# Youtube_Top.net
KiCad netlist of a schematic drawn in Altium Designer
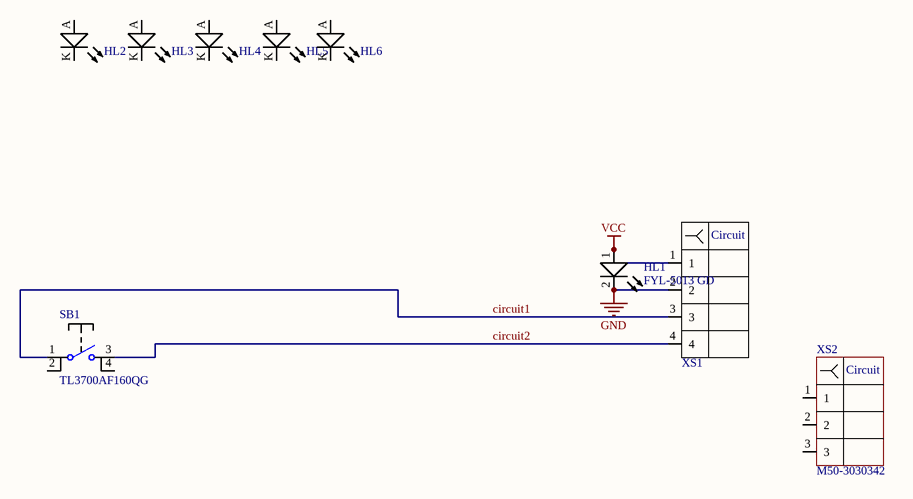
[diagram p0: Youtube_Top.SchDoc]

(export (version "E")
  (design (tool "Eeschema 10.0.6"))
  (components
    (comp (ref "HL1")
      (value "FYL-5013 GD")
      (footprint "LED_3MM_GREEN")
      (libsource (lib "SssAccesDatbase") (part "LED_12"))
    )
    (comp (ref "HL2")
      (value "RD 0603")
      (footprint "LED-0603-RED")
      (description "LED RED DIFFUSED 0603 SMD")
      (fields
        (field (name "PART NUMBER") "150060RS55040")
        (field (name "DIGI-KEY PART NUMBER") "732-12015-1-ND")
      )
      (libsource (lib "SssAccesDatbase") (part "LED_AK"))
    )
    (comp (ref "HL3")
      (value "RD 0603")
      (footprint "LED-0603-RED")
      (description "LED RED DIFFUSED 0603 SMD")
      (fields
        (field (name "PART NUMBER") "150060RS55040")
        (field (name "DIGI-KEY PART NUMBER") "732-12015-1-ND")
      )
      (libsource (lib "SssAccesDatbase") (part "LED_AK"))
    )
    (comp (ref "HL4")
      (value "RD 0603")
      (footprint "LED-0603-RED")
      (description "LED RED DIFFUSED 0603 SMD")
      (fields
        (field (name "PART NUMBER") "150060RS55040")
        (field (name "DIGI-KEY PART NUMBER") "732-12015-1-ND")
      )
      (libsource (lib "SssAccesDatbase") (part "LED_AK"))
    )
    (comp (ref "HL5")
      (value "RD 0603")
      (footprint "LED-0603-RED")
      (description "LED RED DIFFUSED 0603 SMD")
      (fields
        (field (name "PART NUMBER") "150060RS55040")
        (field (name "DIGI-KEY PART NUMBER") "732-12015-1-ND")
      )
      (libsource (lib "SssAccesDatbase") (part "LED_AK"))
    )
    (comp (ref "HL6")
      (value "RD 0603")
      (footprint "LED-0603-RED")
      (description "LED RED DIFFUSED 0603 SMD")
      (fields
        (field (name "PART NUMBER") "150060RS55040")
        (field (name "DIGI-KEY PART NUMBER") "732-12015-1-ND")
      )
      (libsource (lib "SssAccesDatbase") (part "LED_AK"))
    )
    (comp (ref "SB1")
      (value "TL3700AF160QG")
      (footprint "TL3700AF160QG")
      (description "SWITCH TACTILE SPST-NO 0.02A 15V")
      (fields (field (name "DIGI-KEY PART NUMBER") "EG4919CT-ND"))
      (libsource (lib "SssAccesDatbase") (part "SW-SPST_1"))
    )
    (comp (ref "XS1")
      (value "PBS-4")
      (footprint "PBS-4-3D")
      (description "Headers & Wire Housings 4 PIN SIL VERTICAL SOCKET GOLD+TIN")
      (fields
        (field (name "PART NUMBER") "M20-7820442")
        (field (name "MOUSER PART NUMBER") "855-M20-7820442")
      )
      (libsource (lib "SssAccesDatbase") (part "XS-4"))
    )
    (comp (ref "XS2")
      (value "M50-3030342")
      (footprint "PBLS-1.27-3")
      (description "Headers & Wire Housings 3 WAY SIL VERT PC TAIL SKT")
      (fields (field (name "MOUSER PART NUMBER") "855-M50-3030342"))
      (libsource (lib "SssAccesDatbase") (part "XS-3"))
    )
  )
  (nets
    (net (code "1") (name "/circuit1") (class "Default")
      (node (ref "SB1") (pin "1") (pinfunction "COMMON_1") (pintype "passive"))
      (node (ref "XS1") (pin "3") (pinfunction "3_3") (pintype "passive"))
    )
    (net (code "2") (name "/circuit2") (class "Default")
      (node (ref "SB1") (pin "3") (pinfunction "COMMON_3") (pintype "passive"))
      (node (ref "XS1") (pin "4") (pinfunction "4_4") (pintype "passive"))
    )
    (net (code "3") (name "GND") (class "Default")
      (node (ref "HL1") (pin "2") (pinfunction "K_2") (pintype "passive"))
      (node (ref "XS1") (pin "2") (pinfunction "2_2") (pintype "passive"))
    )
    (net (code "4") (name "VCC") (class "Default")
      (node (ref "HL1") (pin "1") (pinfunction "A_1") (pintype "passive"))
      (node (ref "XS1") (pin "1") (pinfunction "1_1") (pintype "passive"))
    )
    (net (code "5") (name "unconnected-(HL2-PadA)") (class "Default")
      (node (ref "HL2") (pin "A") (pinfunction "A_A") (pintype "passive"))
    )
    (net (code "6") (name "unconnected-(HL2-PadK)") (class "Default")
      (node (ref "HL2") (pin "K") (pinfunction "K_K") (pintype "passive"))
    )
    (net (code "7") (name "unconnected-(HL3-PadA)") (class "Default")
      (node (ref "HL3") (pin "A") (pinfunction "A_A") (pintype "passive"))
    )
    (net (code "8") (name "unconnected-(HL3-PadK)") (class "Default")
      (node (ref "HL3") (pin "K") (pinfunction "K_K") (pintype "passive"))
    )
    (net (code "9") (name "unconnected-(HL4-PadA)") (class "Default")
      (node (ref "HL4") (pin "A") (pinfunction "A_A") (pintype "passive"))
    )
    (net (code "10") (name "unconnected-(HL4-PadK)") (class "Default")
      (node (ref "HL4") (pin "K") (pinfunction "K_K") (pintype "passive"))
    )
    (net (code "11") (name "unconnected-(HL5-PadA)") (class "Default")
      (node (ref "HL5") (pin "A") (pinfunction "A_A") (pintype "passive"))
    )
    (net (code "12") (name "unconnected-(HL5-PadK)") (class "Default")
      (node (ref "HL5") (pin "K") (pinfunction "K_K") (pintype "passive"))
    )
    (net (code "13") (name "unconnected-(HL6-PadA)") (class "Default")
      (node (ref "HL6") (pin "A") (pinfunction "A_A") (pintype "passive"))
    )
    (net (code "14") (name "unconnected-(HL6-PadK)") (class "Default")
      (node (ref "HL6") (pin "K") (pinfunction "K_K") (pintype "passive"))
    )
    (net (code "15") (name "unconnected-(SB1-COMMON-Pad4)") (class "Default")
      (node (ref "SB1") (pin "4") (pinfunction "COMMON_4") (pintype "passive"))
    )
    (net (code "16") (name "unconnected-(SB1-NO-Pad2)") (class "Default")
      (node (ref "SB1") (pin "2") (pinfunction "NO_2") (pintype "passive"))
    )
    (net (code "17") (name "unconnected-(XS2-Pad1)") (class "Default")
      (node (ref "XS2") (pin "1") (pinfunction "1_1") (pintype "passive"))
    )
    (net (code "18") (name "unconnected-(XS2-Pad2)") (class "Default")
      (node (ref "XS2") (pin "2") (pinfunction "2_2") (pintype "passive"))
    )
    (net (code "19") (name "unconnected-(XS2-Pad3)") (class "Default")
      (node (ref "XS2") (pin "3") (pinfunction "3_3") (pintype "passive"))
    )
  )
)
